# MS5803_board.net
KiCad netlist of a schematic drawn in EAGLE
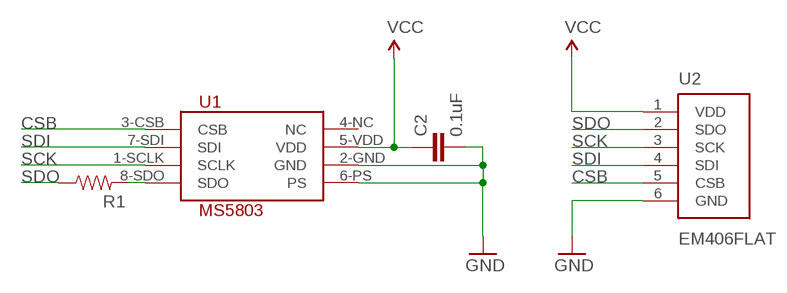
[diagram p0: schematic, sheet 1]

(export (version "E")
  (design (tool "Eeschema 10.0.6"))
  (components
    (comp (ref "C2")
      (value "0.1uF")
      (footprint "eagle-import:0603-CAP")
      (libsource (lib "eagle-import") (part "CAP0603-CAP"))
    )
    (comp (ref "R1")
      (value "0")
      (footprint "eagle-import:0603-RES")
      (libsource (lib "eagle-import") (part "RESISTOR0603-RES"))
    )
    (comp (ref "U1")
      (value "MS5803")
      (footprint "eagle-import:MS5803")
      (libsource (lib "eagle-import") (part "MS5803"))
    )
    (comp (ref "U2")
      (value "EM406FLAT")
      (footprint "eagle-import:EM406-FLAT")
      (libsource (lib "eagle-import") (part "EM406FLAT"))
    )
  )
  (nets
    (net (code "1") (name "/CSB") (class "Default")
      (node (ref "U1") (pin "3-CSB") (pinfunction "CSB_3-CSB") (pintype "bidirectional"))
      (node (ref "U2") (pin "5") (pinfunction "CSB_5") (pintype "bidirectional"))
    )
    (net (code "2") (name "/SCK") (class "Default")
      (node (ref "U1") (pin "1-SCLK") (pinfunction "SCLK_1-SCLK") (pintype "bidirectional"))
      (node (ref "U2") (pin "3") (pinfunction "SCK_3") (pintype "bidirectional"))
    )
    (net (code "3") (name "/SDI") (class "Default")
      (node (ref "U1") (pin "7-SDI") (pinfunction "SDI_7-SDI") (pintype "bidirectional"))
      (node (ref "U2") (pin "4") (pinfunction "SDI_4") (pintype "bidirectional"))
    )
    (net (code "4") (name "/SDO") (class "Default")
      (node (ref "R1") (pin "1") (pinfunction "1_1") (pintype "passive"))
      (node (ref "U2") (pin "2") (pinfunction "SDO_2") (pintype "bidirectional"))
    )
    (net (code "5") (name "GND") (class "Default")
      (node (ref "C2") (pin "2") (pinfunction "2_2") (pintype "passive"))
      (node (ref "U1") (pin "2-GND") (pinfunction "GND_2-GND") (pintype "bidirectional"))
      (node (ref "U1") (pin "6-PS") (pinfunction "PS_6-PS") (pintype "bidirectional"))
      (node (ref "U2") (pin "6") (pinfunction "GND_6") (pintype "bidirectional"))
    )
    (net (code "6") (name "Net-(U1-SDO)") (class "Default")
      (node (ref "R1") (pin "2") (pinfunction "2_2") (pintype "passive"))
      (node (ref "U1") (pin "8-SDO") (pinfunction "SDO_8-SDO") (pintype "bidirectional"))
    )
    (net (code "7") (name "VCC") (class "Default")
      (node (ref "C2") (pin "1") (pinfunction "1_1") (pintype "passive"))
      (node (ref "U1") (pin "5-VDD") (pinfunction "VDD_5-VDD") (pintype "bidirectional"))
      (node (ref "U2") (pin "1") (pinfunction "VDD_1") (pintype "bidirectional"))
    )
    (net (code "8") (name "unconnected-(U1-NC-Pad4-NC)") (class "Default")
      (node (ref "U1") (pin "4-NC") (pinfunction "NC_4-NC") (pintype "bidirectional"))
    )
  )
)
